# schematic.net
KiCad netlist of a schematic drawn in EasyEDA
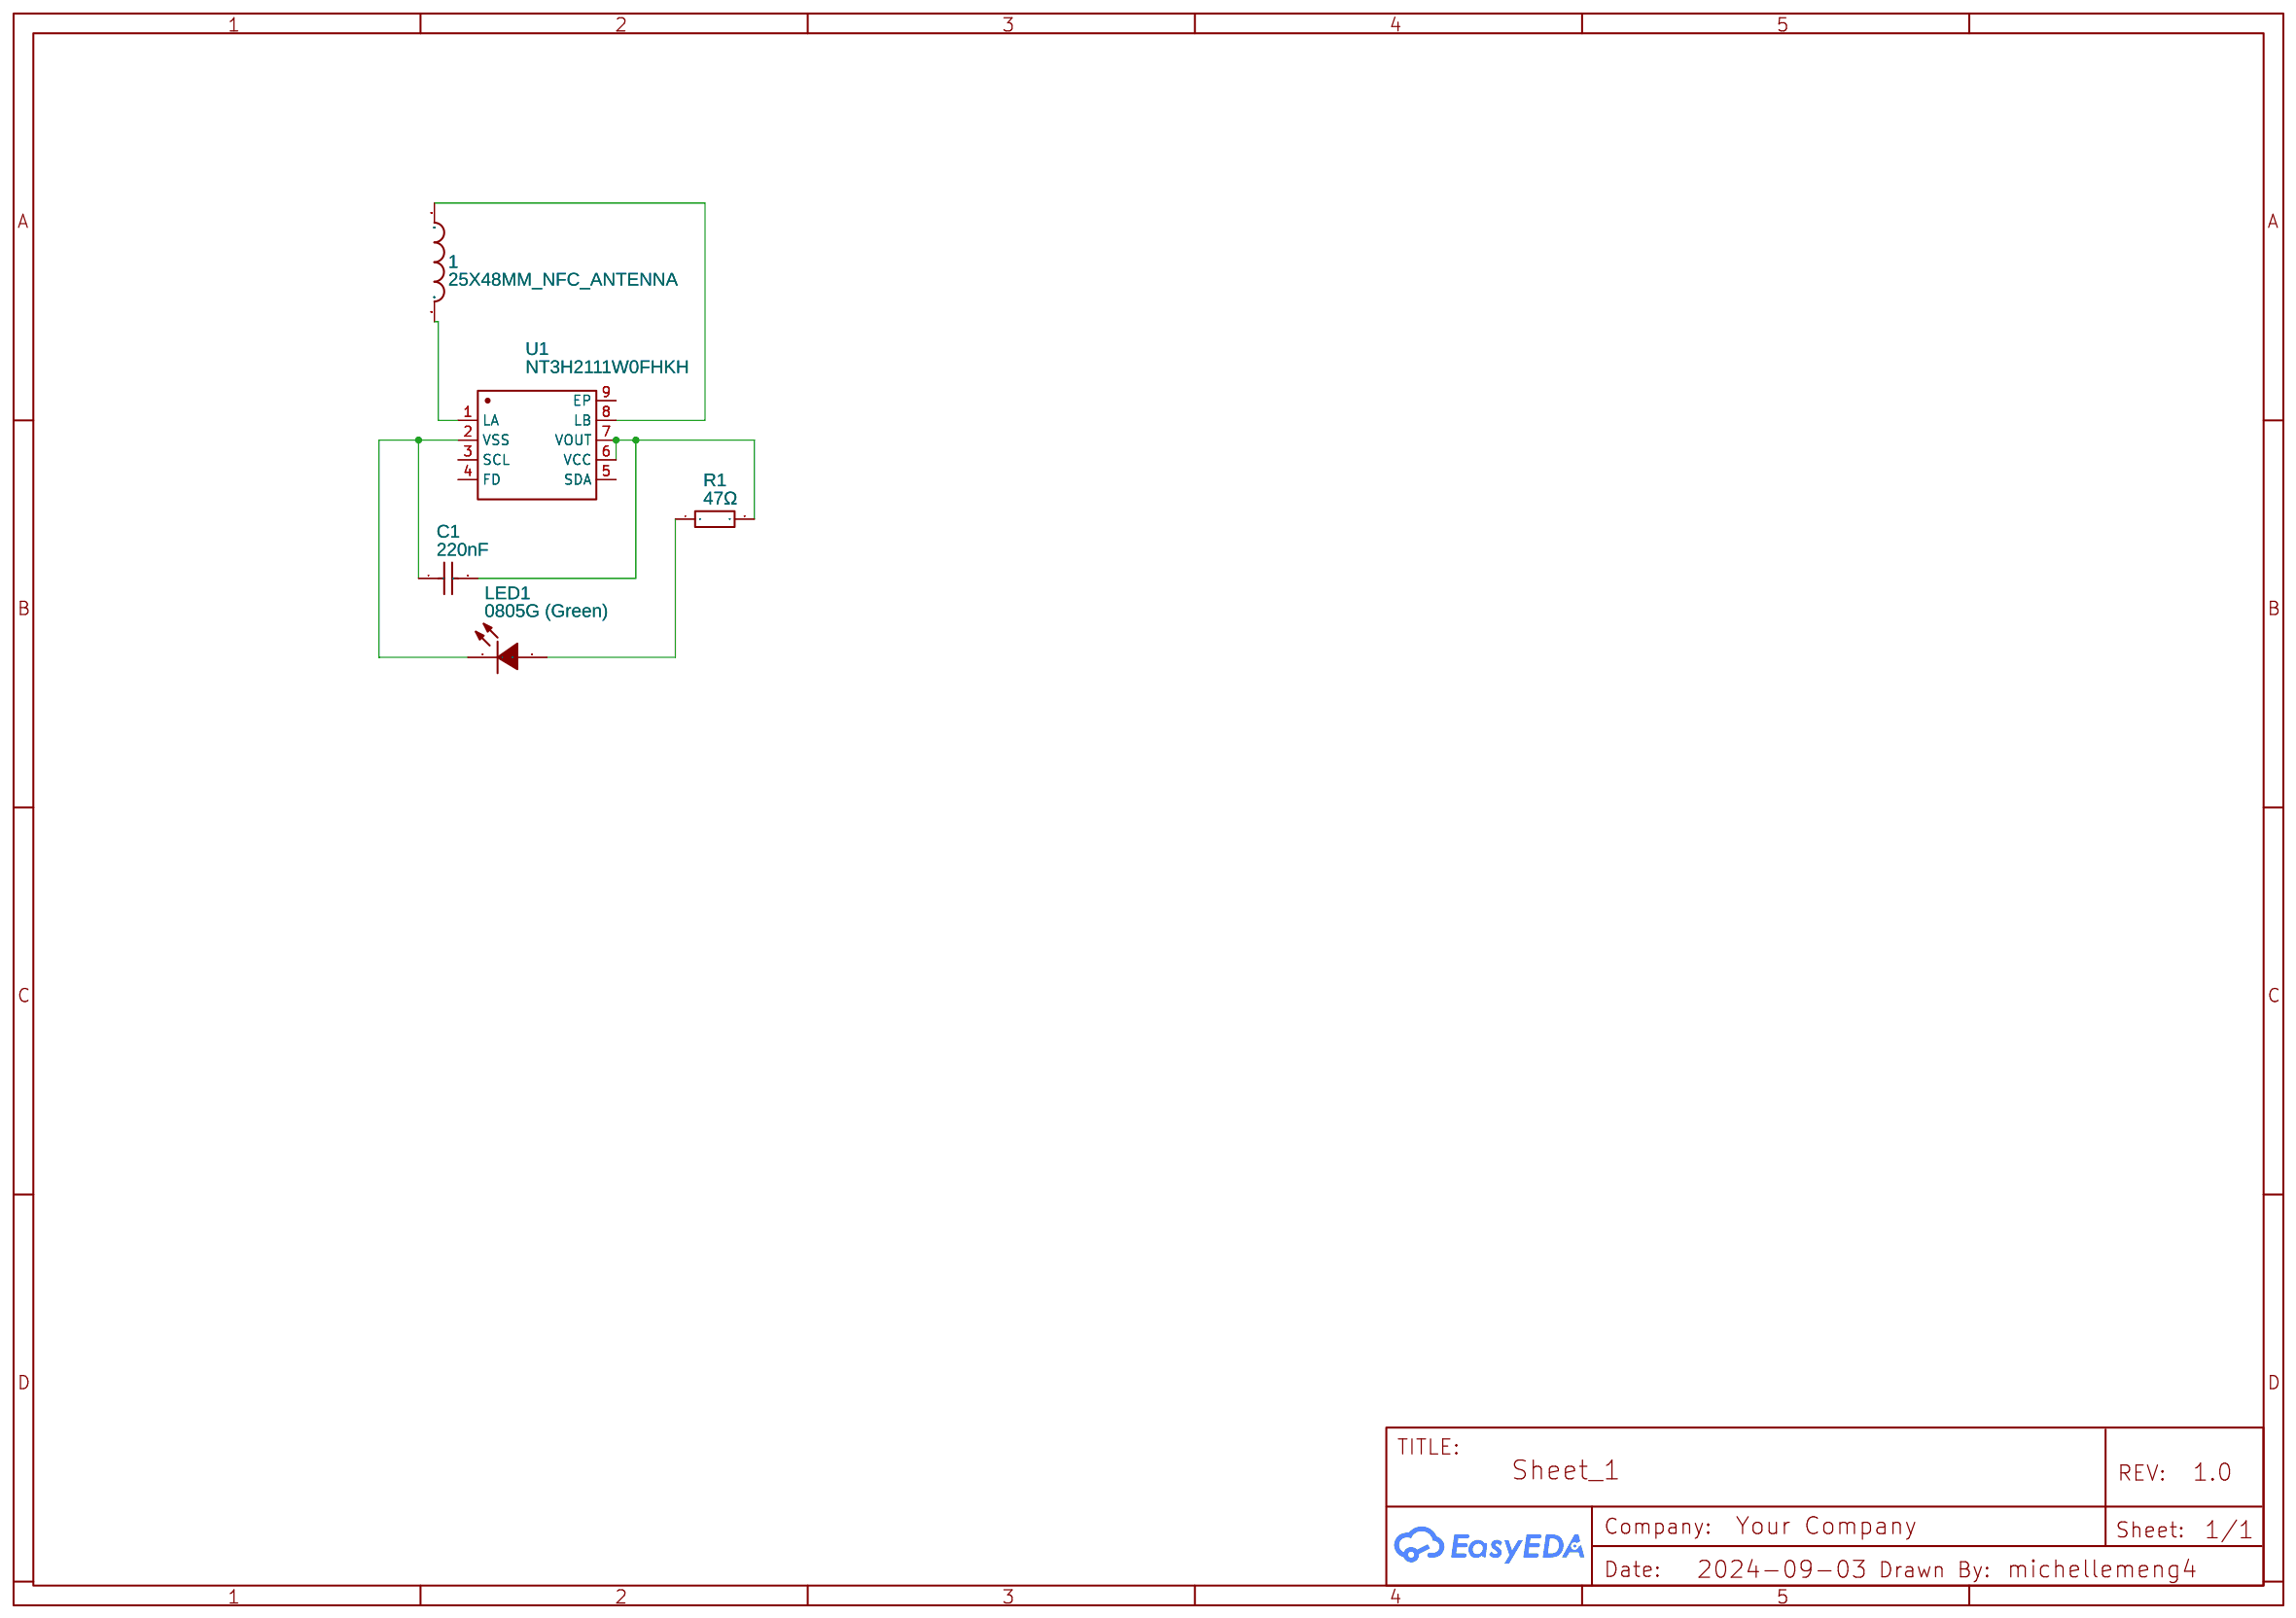
[diagram p0: schematic sheet]

(export (version "E")
  (design (tool "Eeschema 10.0.6"))
  (components
    (comp (ref "1") (value "25X48MM_NFC_ANTENNA") (libsource (lib "") (part "25X48MM_NFC_ANTENNA")))
    (comp (ref "C1")
      (value "220nF")
      (fields
        (field (name "Manufacturer Part") "CL10B224KA8NNNC")
        (field (name "Manufacturer") "SAMSUNG(三星)")
      )
      (libsource (lib "") (part "CL10B224KA8NNNC"))
    )
    (comp (ref "LED1")
      (value "0805G (Green)")
      (fields (field (name "Manufacturer Part") "KT-0805G") (field (name "Manufacturer") "KENTO"))
      (libsource (lib "") (part "0805G (Green)"))
    )
    (comp (ref "R1")
      (value "47Ω")
      (fields
        (field (name "Manufacturer Part") "0603WAF470JT5E")
        (field (name "Manufacturer") "UNI-ROYAL(厚声)")
      )
      (libsource (lib "") (part "0603WAF470JT5E"))
    )
    (comp (ref "U1")
      (value "NT3H2111W0FHKH")
      (fields (field (name "Manufacturer") "NXP(恩智浦)"))
      (libsource (lib "") (part "NT3H2111W0FHKH"))
    )
  )
  (nets
    (net (code "1") (name "Net-(LED1-A)") (class "Default")
      (node (ref "LED1") (pin "1") (pinfunction "A_1") (pintype "unspecified"))
      (node (ref "R1") (pin "1") (pinfunction "1_1") (pintype "input"))
    )
    (net (code "2") (name "Net-(LED1-K)") (class "Default")
      (node (ref "C1") (pin "1") (pinfunction "1_1") (pintype "input"))
      (node (ref "LED1") (pin "2") (pinfunction "K_2") (pintype "unspecified"))
      (node (ref "U1") (pin "2") (pinfunction "VSS_2") (pintype "unspecified"))
    )
    (net (code "3") (name "Net-(U1-LA)") (class "Default")
      (node (ref "1") (pin "P$2") (pinfunction "P$2_P$2") (pintype "bidirectional"))
      (node (ref "U1") (pin "1") (pinfunction "LA_1") (pintype "unspecified"))
    )
    (net (code "4") (name "Net-(U1-LB)") (class "Default")
      (node (ref "1") (pin "P$1") (pinfunction "P$1_P$1") (pintype "bidirectional"))
      (node (ref "U1") (pin "8") (pinfunction "LB_8") (pintype "unspecified"))
    )
    (net (code "5") (name "Net-(U1-VCC)") (class "Default")
      (node (ref "C1") (pin "2") (pinfunction "2_2") (pintype "input"))
      (node (ref "R1") (pin "2") (pinfunction "2_2") (pintype "input"))
      (node (ref "U1") (pin "6") (pinfunction "VCC_6") (pintype "unspecified"))
      (node (ref "U1") (pin "7") (pinfunction "VOUT_7") (pintype "unspecified"))
    )
    (net (code "6") (name "unconnected-(U1-EP-Pad9)") (class "Default")
      (node (ref "U1") (pin "9") (pinfunction "EP_9") (pintype "unspecified"))
    )
    (net (code "7") (name "unconnected-(U1-FD-Pad4)") (class "Default")
      (node (ref "U1") (pin "4") (pinfunction "FD_4") (pintype "unspecified"))
    )
    (net (code "8") (name "unconnected-(U1-SCL-Pad3)") (class "Default")
      (node (ref "U1") (pin "3") (pinfunction "SCL_3") (pintype "unspecified"))
    )
    (net (code "9") (name "unconnected-(U1-SDA-Pad5)") (class "Default")
      (node (ref "U1") (pin "5") (pinfunction "SDA_5") (pintype "unspecified"))
    )
  )
)
